# LMAT_AMT_V4.net
KiCad netlist of a schematic drawn in Altium Designer
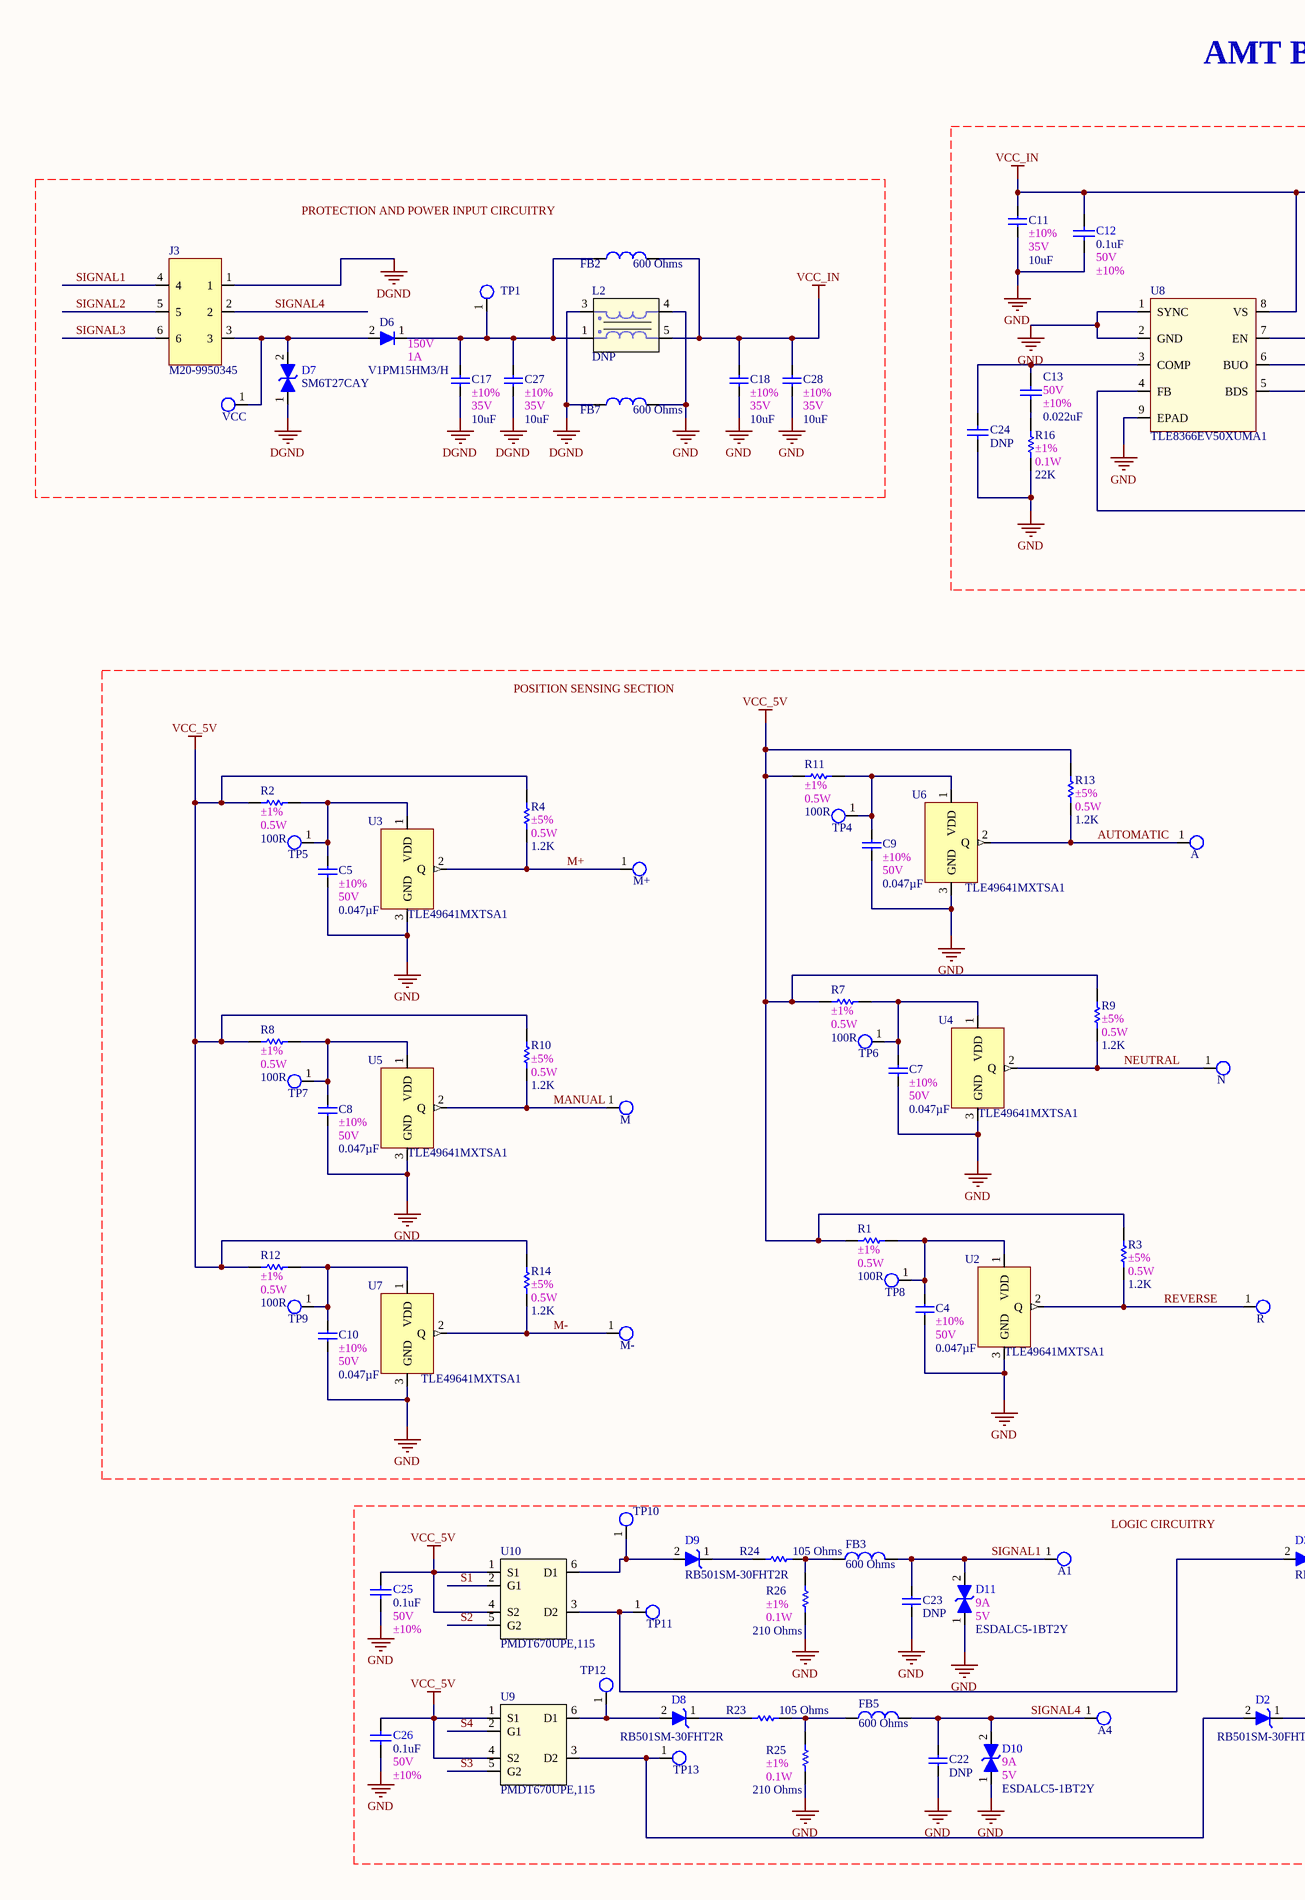
[diagram p0: LMAT_AMT_V4.SchDoc, left]
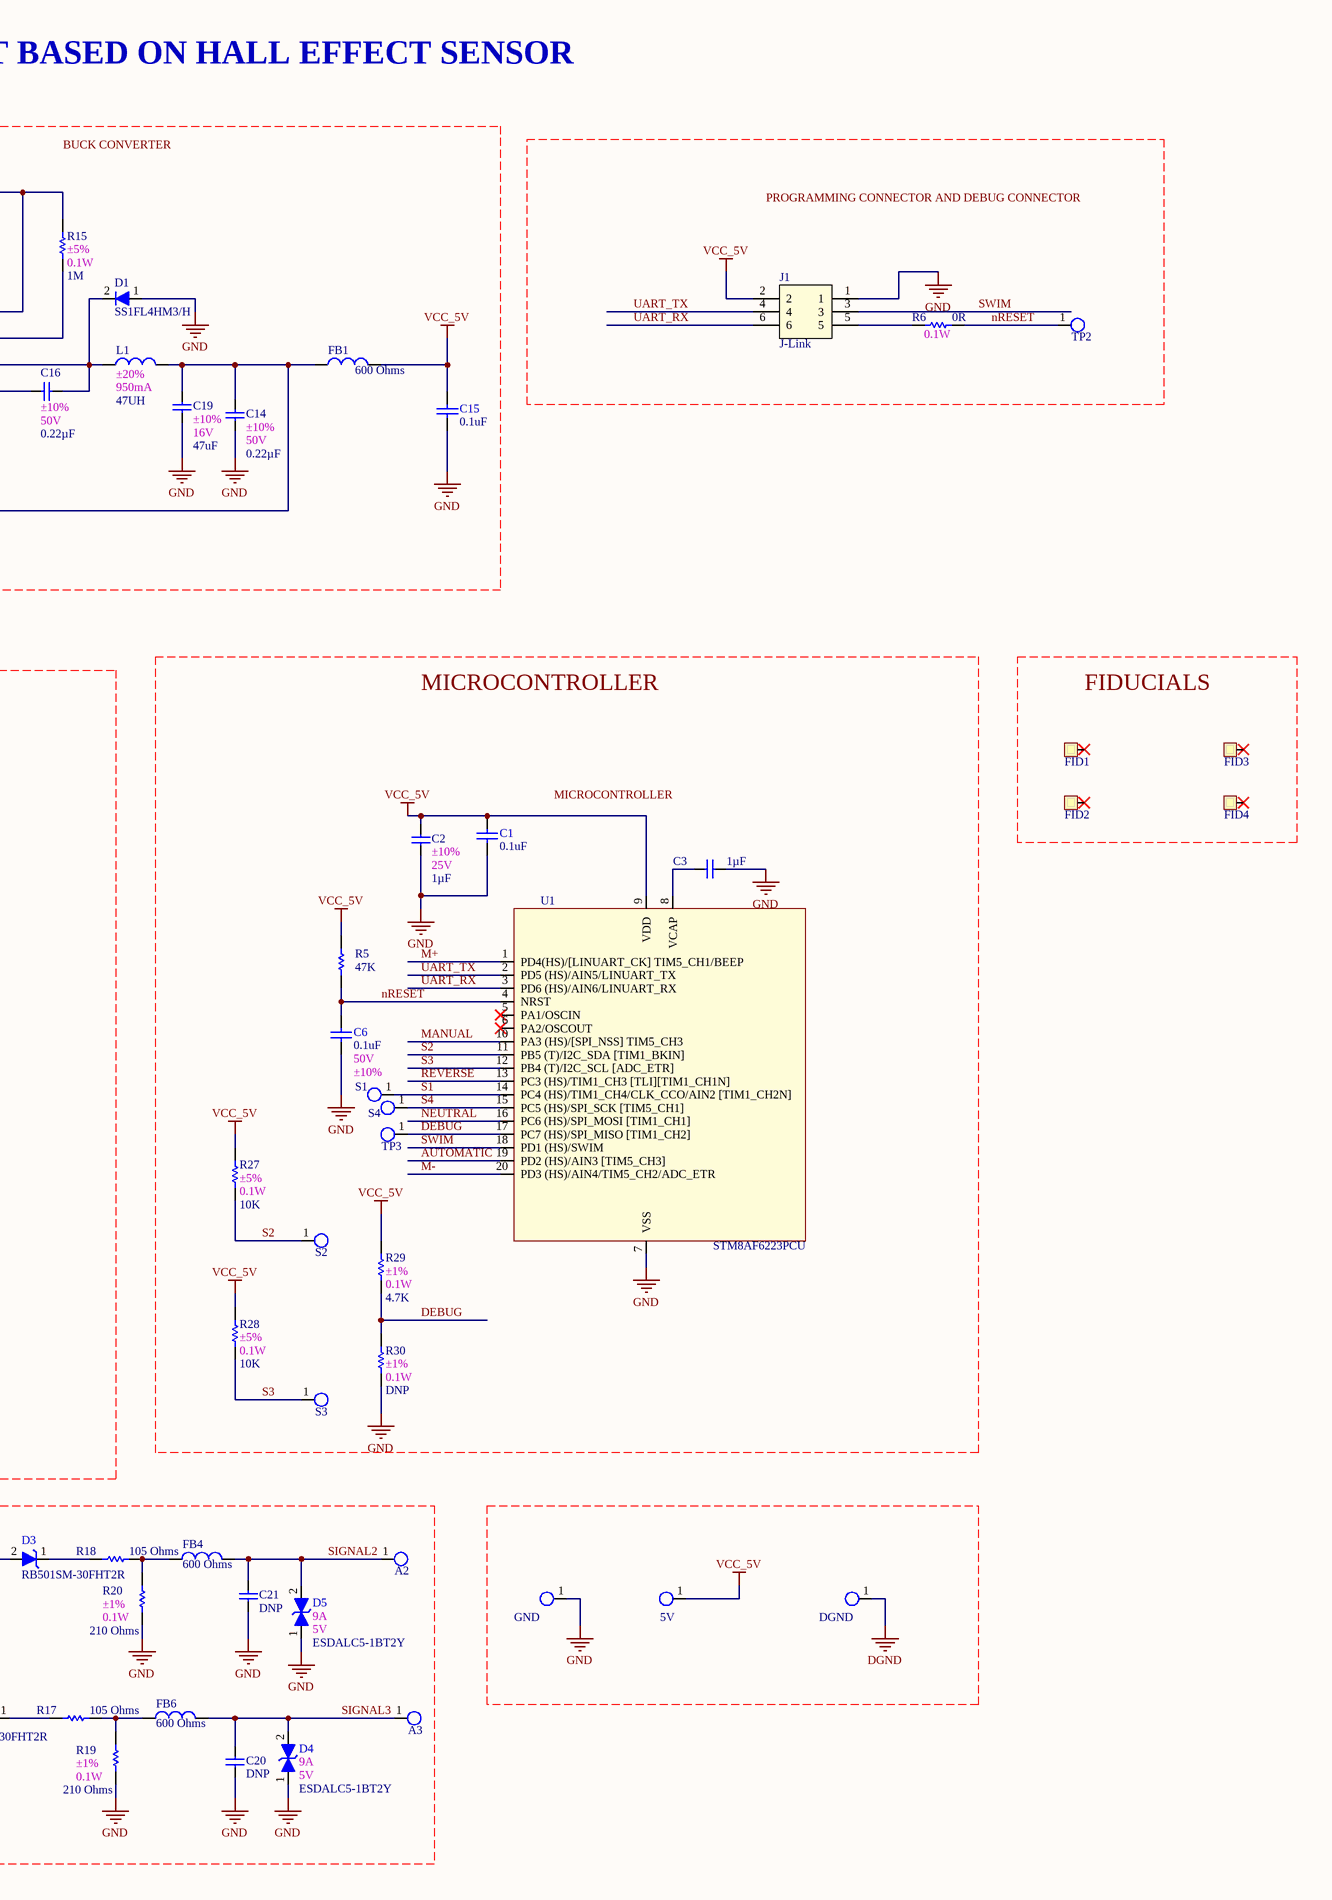
[diagram p1: LMAT_AMT_V4.SchDoc, right]

(export (version "E")
  (design (tool "Eeschema 10.0.6"))
  (components
    (comp (ref "5V")
      (value "Test Point- 35mil")
      (footprint "TP_40X40")
      (fields (field (name "INTERNAL PART NUMBER") "EMS-TP35MIL-S"))
      (libsource (lib "Integrated_Master_Library") (part "EMS-TP35MIL-S"))
    )
    (comp (ref "A")
      (value "Test Point- 35mil")
      (footprint "TP_40X40")
      (fields (field (name "INTERNAL PART NUMBER") "EMS-TP35MIL-S"))
      (libsource (lib "Integrated_Master_Library") (part "EMS-TP35MIL-S"))
    )
    (comp (ref "A1")
      (value "Test Point- 35mil")
      (footprint "TP_40X40")
      (fields (field (name "INTERNAL PART NUMBER") "EMS-TP35MIL-S"))
      (libsource (lib "Integrated_Master_Library") (part "EMS-TP35MIL-S"))
    )
    (comp (ref "A2")
      (value "Test Point- 35mil")
      (footprint "TP_40X40")
      (fields (field (name "INTERNAL PART NUMBER") "EMS-TP35MIL-S"))
      (libsource (lib "Integrated_Master_Library") (part "EMS-TP35MIL-S"))
    )
    (comp (ref "A3")
      (value "Test Point- 35mil")
      (footprint "TP_40X40")
      (fields (field (name "INTERNAL PART NUMBER") "EMS-TP35MIL-S"))
      (libsource (lib "Integrated_Master_Library") (part "EMS-TP35MIL-S"))
    )
    (comp (ref "A4")
      (value "Test Point- 35mil")
      (footprint "TP_40X40")
      (fields (field (name "INTERNAL PART NUMBER") "EMS-TP35MIL-S"))
      (libsource (lib "Integrated_Master_Library") (part "EMS-TP35MIL-S"))
    )
    (comp (ref "C1")
      (value "0.1uF")
      (footprint "Masterlib_auto:SMDC0603")
      (description "CAP CER 0.1UF 50V 10% X7R 0603")
      (fields
        (field (name "MANUFACTURER PART NUMBER") "CGA3E2X7R1H104K080AA")
        (field (name "MANUFACTURER") "TDK Corporation")
      )
      (libsource (lib "Integrated_Master_Library") (part "ECA0U10K50V0-SC"))
    )
    (comp (ref "C2")
      (value "1µF")
      (footprint "Masterlib_auto:SMDC0603")
      (description "CAP CER 1UF 25V X7R 0603")
      (fields
        (field (name "MANUFACTURER") "TDK Corporation")
        (field (name "VENDOR PART NUMBER") "445-173628-1-ND")
        (field (name "2ND AUXILIARY FIELD") "±10%")
        (field (name "1ST AUXILIARY FIELD") "25V")
      )
      (libsource (lib "Integrated_Master_Library (3)") (part "ECA1U00L25V0-SC"))
    )
    (comp (ref "C3")
      (value "1µF")
      (footprint "Masterlib_auto:SMDC0603")
      (description "CAP CER 1UF 25V X7R 0603")
      (fields
        (field (name "MANUFACTURER") "TDK Corporation")
        (field (name "VENDOR PART NUMBER") "445-173628-1-ND")
      )
      (libsource (lib "Integrated_Master_Library (3)") (part "ECA1U00L25V0-SC"))
    )
    (comp (ref "C4")
      (value "0.047µF")
      (footprint "Masterlib_auto:SMDC0603")
      (description "CAP CER 0.047UF 50V X7R 0603")
      (fields
        (field (name "MANUFACTURER") "TDK Corporation")
        (field (name "VENDOR PART NUMBER") "445-5664-1-ND")
        (field (name "2ND AUXILIARY FIELD") "±10%")
        (field (name "1ST AUXILIARY FIELD") "50V")
      )
      (libsource (lib "Integrated_Master_Library") (part "ECA47N0L50V-SC"))
    )
    (comp (ref "C5")
      (value "0.047µF")
      (footprint "Masterlib_auto:SMDC0603")
      (description "CAP CER 0.047UF 50V X7R 0603")
      (fields
        (field (name "MANUFACTURER") "TDK Corporation")
        (field (name "VENDOR PART NUMBER") "445-5664-1-ND")
        (field (name "2ND AUXILIARY FIELD") "±10%")
        (field (name "1ST AUXILIARY FIELD") "50V")
      )
      (libsource (lib "Integrated_Master_Library") (part "ECA47N0L50V-SC"))
    )
    (comp (ref "C6")
      (value "0.1uF")
      (footprint "Masterlib_auto:SMDC0603")
      (description "CAP CER 0.1UF 50V 10% X7R 0603")
      (fields
        (field (name "MANUFACTURER PART NUMBER") "CGA3E2X7R1H104K080AA")
        (field (name "MANUFACTURER") "TDK Corporation")
        (field (name "1ST AUXILIARY FIELD") "50V")
        (field (name "2ND AUXILIARY FIELD") "±10%")
      )
      (libsource (lib "Integrated_Master_Library") (part "ECA0U10K50V0-SC"))
    )
    (comp (ref "C7")
      (value "0.047µF")
      (footprint "Masterlib_auto:SMDC0603")
      (description "CAP CER 0.047UF 50V X7R 0603")
      (fields
        (field (name "MANUFACTURER") "TDK Corporation")
        (field (name "VENDOR PART NUMBER") "445-5664-1-ND")
        (field (name "2ND AUXILIARY FIELD") "±10%")
        (field (name "1ST AUXILIARY FIELD") "50V")
      )
      (libsource (lib "Integrated_Master_Library") (part "ECA47N0L50V-SC"))
    )
    (comp (ref "C8")
      (value "0.047µF")
      (footprint "Masterlib_auto:SMDC0603")
      (description "CAP CER 0.047UF 50V X7R 0603")
      (fields
        (field (name "MANUFACTURER") "TDK Corporation")
        (field (name "VENDOR PART NUMBER") "445-5664-1-ND")
        (field (name "2ND AUXILIARY FIELD") "±10%")
        (field (name "1ST AUXILIARY FIELD") "50V")
      )
      (libsource (lib "Integrated_Master_Library") (part "ECA47N0L50V-SC"))
    )
    (comp (ref "C9")
      (value "0.047µF")
      (footprint "Masterlib_auto:SMDC0603")
      (description "CAP CER 0.047UF 50V X7R 0603")
      (fields
        (field (name "MANUFACTURER") "TDK Corporation")
        (field (name "VENDOR PART NUMBER") "445-5664-1-ND")
        (field (name "2ND AUXILIARY FIELD") "±10%")
        (field (name "1ST AUXILIARY FIELD") "50V")
      )
      (libsource (lib "Integrated_Master_Library") (part "ECA47N0L50V-SC"))
    )
    (comp (ref "C10")
      (value "0.047µF")
      (footprint "Masterlib_auto:SMDC0603")
      (description "CAP CER 0.047UF 50V X7R 0603")
      (fields
        (field (name "MANUFACTURER") "TDK Corporation")
        (field (name "VENDOR PART NUMBER") "445-5664-1-ND")
        (field (name "2ND AUXILIARY FIELD") "±10%")
        (field (name "1ST AUXILIARY FIELD") "50V")
      )
      (libsource (lib "Integrated_Master_Library") (part "ECA47N0L50V-SC"))
    )
    (comp (ref "C11")
      (value "10uF")
      (footprint "Master_Library:SMDC1206")
      (description "CAP CER 10UF 35V X7R 1206")
      (fields
        (field (name "MANUFACTURER") "TDK Corporation")
        (field (name "VENDOR PART NUMBER") "445-174428-1-ND")
        (field (name "2ND AUXILIARY FIELD") "±10%")
        (field (name "1ST AUXILIARY FIELD") "35V")
      )
      (libsource (lib "Master_ Library") (part "ECA10U0L35V0-SG"))
    )
    (comp (ref "C12")
      (value "0.1uF")
      (footprint "Masterlib_auto:SMDC0603")
      (description "CAP CER 0.1UF 50V 10% X7R 0603")
      (fields
        (field (name "MANUFACTURER PART NUMBER") "CGA3E2X7R1H104K080AA")
        (field (name "MANUFACTURER") "TDK Corporation")
        (field (name "1ST AUXILIARY FIELD") "50V")
        (field (name "2ND AUXILIARY FIELD") "±10%")
      )
      (libsource (lib "Integrated_Master_Library") (part "ECA0U10K50V0-SC"))
    )
    (comp (ref "C13")
      (value "0.022uF")
      (footprint "Masterlib_auto:SMDC0603")
      (description "CAP CER 0.022UF 50V 10% X7R 0603")
      (fields
        (field (name "MANUFACTURER PART NUMBER") "CGA3E2X7R1H223K080AA")
        (field (name "MANUFACTURER") "TDK Corporation")
        (field (name "1ST AUXILIARY FIELD") "50V")
        (field (name "2ND AUXILIARY FIELD") "±10%")
      )
      (libsource (lib "Integrated_Master_Library") (part "ECA0U022K50V0-SC"))
    )
    (comp (ref "C14")
      (value "0.22µF")
      (footprint "Masterlib_auto:SMDC0603")
      (description "CAP CER 0.22UF 50V X7R 0603")
      (fields
        (field (name "MANUFACTURER") "Murata Electronics North America")
        (field (name "VENDOR PART NUMBER") "490-14410-1-ND")
        (field (name "2ND AUXILIARY FIELD") "±10%")
        (field (name "1ST AUXILIARY FIELD") "50V")
      )
      (libsource (lib "Integrated_Master_Library (3)") (part "ECA0U22L50V0-SC"))
    )
    (comp (ref "C15")
      (value "0.1uF")
      (footprint "Masterlib_auto:SMDC0603")
      (description "CAP CER 0.1UF 50V 10% X7R 0603")
      (fields
        (field (name "MANUFACTURER PART NUMBER") "CGA3E2X7R1H104K080AA")
        (field (name "MANUFACTURER") "TDK Corporation")
      )
      (libsource (lib "Integrated_Master_Library") (part "ECA0U10K50V0-SC"))
    )
    (comp (ref "C16")
      (value "0.22µF")
      (footprint "Masterlib_auto:SMDC0603")
      (description "CAP CER 0.22UF 50V X7R 0603")
      (fields
        (field (name "MANUFACTURER") "Murata Electronics North America")
        (field (name "VENDOR PART NUMBER") "490-14410-1-ND")
        (field (name "2ND AUXILIARY FIELD") "±10%")
        (field (name "1ST AUXILIARY FIELD") "50V")
      )
      (libsource (lib "Integrated_Master_Library") (part "ECA0U22L50V0-SC"))
    )
    (comp (ref "C17")
      (value "10uF")
      (footprint "Master_Library:SMDC1206")
      (description "CAP CER 10UF 35V X7R 1206")
      (fields
        (field (name "MANUFACTURER") "TDK Corporation")
        (field (name "VENDOR PART NUMBER") "445-174428-1-ND")
        (field (name "2ND AUXILIARY FIELD") "±10%")
        (field (name "1ST AUXILIARY FIELD") "35V")
      )
      (libsource (lib "Master_ Library") (part "ECA10U0L35V0-SG"))
    )
    (comp (ref "C18")
      (value "10uF")
      (footprint "Master_Library:SMDC1206")
      (description "CAP CER 10UF 35V X7R 1206")
      (fields
        (field (name "MANUFACTURER") "TDK Corporation")
        (field (name "VENDOR PART NUMBER") "445-174428-1-ND")
        (field (name "2ND AUXILIARY FIELD") "±10%")
        (field (name "1ST AUXILIARY FIELD") "35V")
      )
      (libsource (lib "Master_ Library") (part "ECA10U0L35V0-SG"))
    )
    (comp (ref "C19")
      (value "47uF")
      (footprint "Master_Library:SMDC1210")
      (description "CAP CER 47UF 16V X6S 1210")
      (fields
        (field (name "MANUFACTURER") "Murata Electronics North America")
        (field (name "VENDOR PART NUMBER") "490-12494-1-ND")
        (field (name "2ND AUXILIARY FIELD") "±10%")
        (field (name "1ST AUXILIARY FIELD") "16V")
      )
      (libsource (lib "Automobile-ML") (part "ECA47U0L16V0-SH"))
    )
    (comp (ref "C20")
      (value "DNP")
      (footprint "Masterlib_auto:SMDC0603")
      (description "CAP CER 10000PF 50V X8R 0603")
      (fields
        (field (name "MANUFACTURER") "TDK Corporation")
        (field (name "VENDOR PART NUMBER") "445-5892-1-ND")
      )
      (libsource (lib "Automobile-ML") (part "ECA0U01L50V0-SC"))
    )
    (comp (ref "C21")
      (value "DNP")
      (footprint "Masterlib_auto:SMDC0603")
      (description "CAP CER 10000PF 50V X8R 0603")
      (fields
        (field (name "MANUFACTURER") "TDK Corporation")
        (field (name "VENDOR PART NUMBER") "445-5892-1-ND")
      )
      (libsource (lib "Automobile-ML") (part "ECA0U01L50V0-SC"))
    )
    (comp (ref "C22")
      (value "DNP")
      (footprint "Masterlib_auto:SMDC0603")
      (description "CAP CER 10000PF 50V X8R 0603")
      (fields
        (field (name "MANUFACTURER") "TDK Corporation")
        (field (name "VENDOR PART NUMBER") "445-5892-1-ND")
      )
      (libsource (lib "Automobile-ML") (part "ECA0U01L50V0-SC"))
    )
    (comp (ref "C23")
      (value "DNP")
      (footprint "Masterlib_auto:SMDC0603")
      (description "CAP CER 10000PF 50V X8R 0603")
      (fields
        (field (name "MANUFACTURER") "TDK Corporation")
        (field (name "VENDOR PART NUMBER") "445-5892-1-ND")
      )
      (libsource (lib "Automobile-ML") (part "ECA0U01L50V0-SC"))
    )
    (comp (ref "C24")
      (value "DNP")
      (footprint "Masterlib_auto:SMDC0603")
      (description "CAP CER 0.022UF 50V 10% X7R 0603")
      (fields
        (field (name "MANUFACTURER PART NUMBER") "CGA3E2X7R1H223K080AA")
        (field (name "MANUFACTURER") "TDK Corporation")
      )
      (libsource (lib "Integrated_Master_Library") (part "ECA0U022K50V0-SC"))
    )
    (comp (ref "C25")
      (value "0.1uF")
      (footprint "Masterlib_auto:SMDC0603")
      (description "CAP CER 0.1UF 50V 10% X7R 0603")
      (fields
        (field (name "MANUFACTURER PART NUMBER") "CGA3E2X7R1H104K080AA")
        (field (name "MANUFACTURER") "TDK Corporation")
        (field (name "1ST AUXILIARY FIELD") "50V")
        (field (name "2ND AUXILIARY FIELD") "±10%")
      )
      (libsource (lib "Integrated_Master_Library") (part "ECA0U10K50V0-SC"))
    )
    (comp (ref "C26")
      (value "0.1uF")
      (footprint "Masterlib_auto:SMDC0603")
      (description "CAP CER 0.1UF 50V 10% X7R 0603")
      (fields
        (field (name "MANUFACTURER PART NUMBER") "CGA3E2X7R1H104K080AA")
        (field (name "MANUFACTURER") "TDK Corporation")
        (field (name "1ST AUXILIARY FIELD") "50V")
        (field (name "2ND AUXILIARY FIELD") "±10%")
      )
      (libsource (lib "Integrated_Master_Library") (part "ECA0U10K50V0-SC"))
    )
    (comp (ref "C27")
      (value "10uF")
      (footprint "Master_Library:SMDC1206")
      (description "CAP CER 10UF 35V X7R 1206")
      (fields
        (field (name "MANUFACTURER") "TDK Corporation")
        (field (name "VENDOR PART NUMBER") "445-174428-1-ND")
        (field (name "2ND AUXILIARY FIELD") "±10%")
        (field (name "1ST AUXILIARY FIELD") "35V")
      )
      (libsource (lib "Master_ Library") (part "ECA10U0L35V0-SG"))
    )
    (comp (ref "C28")
      (value "10uF")
      (footprint "Master_Library:SMDC1206")
      (description "CAP CER 10UF 35V X7R 1206")
      (fields
        (field (name "MANUFACTURER") "TDK Corporation")
        (field (name "VENDOR PART NUMBER") "445-174428-1-ND")
        (field (name "2ND AUXILIARY FIELD") "±10%")
        (field (name "1ST AUXILIARY FIELD") "35V")
      )
      (libsource (lib "Master_ Library") (part "ECA10U0L35V0-SG"))
    )
    (comp (ref "D1")
      (value "SS1FL4HM3/H")
      (footprint "Masterlib_auto:SODFL370X110-2N")
      (description "DIODE SCHOTTKY 40V 1A DO-219AB")
      (fields
        (field (name "MANUFACTURER") "Vishay Semiconductor Diodes Division")
        (field (name "INTERNAL PART NUMBER") "EDDVS1A0040V0-S")
      )
      (libsource (lib "Integrated_Master_Library (3)") (part "EDDVS1A0040V0-S"))
    )
    (comp (ref "D2")
      (value "RB501SM-30FHT2R")
      (footprint "Masterlib_auto:SOD1700X70N-V2")
      (description "Diode Schottky 30V 100mA Surface Mount EMD2")
      (fields
        (field (name "MANUFACTURER") "Rohm Semiconductor")
        (field (name "INTERNAL PART NUMBER") "EDDR0A1030V0-S")
      )
      (libsource (lib "Integrated_Master_Library (3)") (part "EDDR0A1030V0-S"))
    )
    (comp (ref "D3")
      (value "RB501SM-30FHT2R")
      (footprint "Masterlib_auto:SOD1700X70N-V2")
      (description "Diode Schottky 30V 100mA Surface Mount EMD2")
      (fields
        (field (name "MANUFACTURER") "Rohm Semiconductor")
        (field (name "INTERNAL PART NUMBER") "EDDR0A1030V0-S")
      )
      (libsource (lib "Integrated_Master_Library (3)") (part "EDDR0A1030V0-S"))
    )
    (comp (ref "D4")
      (value "ESDALC5-1BT2Y")
      (footprint "Master_Library:SOD1510X40")
      (description "TVS DIODE 5V 17.5V SOD882T")
      (fields
        (field (name "MANUFACTURER") "STMicroelectronics")
        (field (name "INTERNAL PART NUMBER") "EDDST9A005V00-S")
        (field (name "2ND AUXILIARY FIELD") "9A")
        (field (name "1ST AUXILIARY FIELD") "5V")
      )
      (libsource (lib "Master_ Library") (part "EDDST9A005V00-S"))
    )
    (comp (ref "D5")
      (value "ESDALC5-1BT2Y")
      (footprint "Master_Library:SOD1510X40")
      (description "TVS DIODE 5V 17.5V SOD882T")
      (fields
        (field (name "MANUFACTURER") "STMicroelectronics")
        (field (name "INTERNAL PART NUMBER") "EDDST9A005V00-S")
        (field (name "2ND AUXILIARY FIELD") "9A")
        (field (name "1ST AUXILIARY FIELD") "5V")
      )
      (libsource (lib "Master_ Library") (part "EDDST9A005V00-S"))
    )
    (comp (ref "D6")
      (value "V1PM15HM3/H")
      (footprint "MICROSMP (DO-219AD)")
      (description "DIODE SCHOTTKY 150V 1A MICROSMP")
      (fields
        (field (name "MANUFACTURER") "Vishay Semiconductor Diodes Division")
        (field (name "INTERNAL PART NUMBER") "EDDVS1A00150V-S")
        (field (name "1ST AUXILIARY FIELD") "150V")
        (field (name "2ND AUXILIARY FIELD") "1A")
      )
      (libsource (lib "Master_ Library") (part "EDDVS1A00150V-S"))
    )
    (comp (ref "D7")
      (value "SM6T27CAY")
      (footprint "Masterlib_auto:DIOM4336X26B")
      (description "TVS DIODE 23.1V 48.3V SMB")
      (fields
        (field (name "MANUFACTURER") "STMicroelectronics")
        (field (name "INTERNAL PART NUMBER") "EDDST83A025V7-S")
      )
      (libsource (lib "Integrated_Master_Library") (part "EDDST83A025V7-S"))
    )
    (comp (ref "D8")
      (value "RB501SM-30FHT2R")
      (footprint "Masterlib_auto:SOD1700X70N-V2")
      (description "Diode Schottky 30V 100mA Surface Mount EMD2")
      (fields
        (field (name "MANUFACTURER") "Rohm Semiconductor")
        (field (name "INTERNAL PART NUMBER") "EDDR0A1030V0-S")
      )
      (libsource (lib "Integrated_Master_Library (3)") (part "EDDR0A1030V0-S"))
    )
    (comp (ref "D9")
      (value "RB501SM-30FHT2R")
      (footprint "Masterlib_auto:SOD1700X70N-V2")
      (description "Diode Schottky 30V 100mA Surface Mount EMD2")
      (fields
        (field (name "MANUFACTURER") "Rohm Semiconductor")
        (field (name "INTERNAL PART NUMBER") "EDDR0A1030V0-S")
      )
      (libsource (lib "Integrated_Master_Library (3)") (part "EDDR0A1030V0-S"))
    )
    (comp (ref "D10")
      (value "ESDALC5-1BT2Y")
      (footprint "Master_Library:SOD1510X40")
      (description "TVS DIODE 5V 17.5V SOD882T")
      (fields
        (field (name "MANUFACTURER") "STMicroelectronics")
        (field (name "INTERNAL PART NUMBER") "EDDST9A005V00-S")
        (field (name "2ND AUXILIARY FIELD") "9A")
        (field (name "1ST AUXILIARY FIELD") "5V")
      )
      (libsource (lib "Master_ Library") (part "EDDST9A005V00-S"))
    )
    (comp (ref "D11")
      (value "ESDALC5-1BT2Y")
      (footprint "Master_Library:SOD1510X40")
      (description "TVS DIODE 5V 17.5V SOD882T")
      (fields
        (field (name "MANUFACTURER") "STMicroelectronics")
        (field (name "INTERNAL PART NUMBER") "EDDST9A005V00-S")
        (field (name "2ND AUXILIARY FIELD") "9A")
        (field (name "1ST AUXILIARY FIELD") "5V")
      )
      (libsource (lib "Master_ Library") (part "EDDST9A005V00-S"))
    )
    (comp (ref "DGND")
      (value "Test Point- 35mil")
      (footprint "TP_40X40")
      (fields (field (name "INTERNAL PART NUMBER") "EMS-TP35MIL-S"))
      (libsource (lib "Integrated_Master_Library") (part "EMS-TP35MIL-S"))
    )
    (comp (ref "FB1")
      (value "600 Ohms")
      (footprint "SMDL0603")
      (description "FERRITE BEAD 600 OHM 0603 1LN")
      (fields
        (field (name "MANUFACTURER") "Würth Elektronik")
        (field (name "INTERNAL PART NUMBER") "EIN600R1A00-SC")
      )
      (libsource (lib "Master_ Library") (part "EIN600R1A00-SC"))
    )
    (comp (ref "FB2")
      (value "600 Ohms")
      (footprint "SMDL0603")
      (description "FERRITE BEAD 600 OHM 0603 1LN")
      (fields
        (field (name "MANUFACTURER") "Würth Elektronik")
        (field (name "INTERNAL PART NUMBER") "EIN600R1A00-SC")
      )
      (libsource (lib "Master_ Library") (part "EIN600R1A00-SC"))
    )
    (comp (ref "FB3")
      (value "600 Ohms")
      (footprint "SMDL0603")
      (description "FERRITE BEAD 600 OHM 0603 1LN")
      (fields
        (field (name "MANUFACTURER") "Würth Elektronik")
        (field (name "INTERNAL PART NUMBER") "EIN600R1A00-SC")
      )
      (libsource (lib "Master_ Library") (part "EIN600R1A00-SC"))
    )
    (comp (ref "FB4")
      (value "600 Ohms")
      (footprint "SMDL0603")
      (description "FERRITE BEAD 600 OHM 0603 1LN")
      (fields
        (field (name "MANUFACTURER") "Würth Elektronik")
        (field (name "INTERNAL PART NUMBER") "EIN600R1A00-SC")
      )
      (libsource (lib "Master_ Library") (part "EIN600R1A00-SC"))
    )
    (comp (ref "FB5")
      (value "600 Ohms")
      (footprint "SMDL0603")
      (description "FERRITE BEAD 600 OHM 0603 1LN")
      (fields
        (field (name "MANUFACTURER") "Würth Elektronik")
        (field (name "INTERNAL PART NUMBER") "EIN600R1A00-SC")
      )
      (libsource (lib "Master_ Library") (part "EIN600R1A00-SC"))
    )
    (comp (ref "FB6")
      (value "600 Ohms")
      (footprint "SMDL0603")
      (description "FERRITE BEAD 600 OHM 0603 1LN")
      (fields
        (field (name "MANUFACTURER") "Würth Elektronik")
        (field (name "INTERNAL PART NUMBER") "EIN600R1A00-SC")
      )
      (libsource (lib "Master_ Library") (part "EIN600R1A00-SC"))
    )
    (comp (ref "FB7")
      (value "600 Ohms")
      (footprint "SMDL0603")
      (description "FERRITE BEAD 600 OHM 0603 1LN")
      (fields
        (field (name "MANUFACTURER") "Würth Elektronik")
        (field (name "INTERNAL PART NUMBER") "EIN600R1A00-SC")
      )
      (libsource (lib "Master_ Library") (part "EIN600R1A00-SC"))
    )
    (comp (ref "FID1")
      (value "FID40X40")
      (footprint "Master_Library:FID40X40")
      (libsource (lib "Master_ Library") (part "FID_40X40"))
    )
    (comp (ref "FID2")
      (value "FID40X40")
      (footprint "Master_Library:FID40X40")
      (libsource (lib "Master_ Library") (part "FID_40X40"))
    )
    (comp (ref "FID3")
      (value "FID40X40")
      (footprint "Master_Library:FID40X40")
      (libsource (lib "Master_ Library") (part "FID_40X40"))
    )
    (comp (ref "FID4")
      (value "FID40X40")
      (footprint "Master_Library:FID40X40")
      (libsource (lib "Master_ Library") (part "FID_40X40"))
    )
    (comp (ref "GND")
      (value "Test Point- 35mil")
      (footprint "TP_40X40")
      (fields (field (name "INTERNAL PART NUMBER") "EMS-TP35MIL-S"))
      (libsource (lib "Integrated_Master_Library") (part "EMS-TP35MIL-S"))
    )
    (comp (ref "J1")
      (value "J-LINK 6-PIN NEEDLE ADAPTER")
      (footprint "PRG_8.06.16 J-LINK 6-PIN NEEDLE ADAPTER")
      (fields
        (field (name "INTERNAL PART NUMBER") "EMS-8.06.16 J-LINK 6-PIN NEEDLE ADAPTER")
        (field (name "MANUFACTURER") "Segger Microcontroller Systems")
        (field (name "VENDOR PART NUMBER") "899-1051-ND")
        (field (name "1ST AUXILIARY FIELD") "J-Link")
      )
      (libsource (lib "Integrated_Master_Library") (part "EMS-8.06.16 J-LINK 6-PIN NEEDLE ADAPTER"))
    )
    (comp (ref "J3")
      (value "CONN HEADER R/A 6POS 2.54MM")
      (footprint "Masterlib_auto:HDRRA6W86P254_2X3_1344X254X528P_Modified")
      (fields
        (field (name "MANUFACTURER") "Harwin Inc.")
        (field (name "INTERNAL PART NUMBER") "ECN-M20-9950345-0003-0060")
        (field (name "VENDOR PART NUMBER") "952-2092-ND")
        (field (name "MANUFACTURER PART NUMBER") "M20-9950345")
      )
      (libsource (lib "Automobile-ML") (part "ECN-M20-9950345-0003-0060"))
    )
    (comp (ref "L1")
      (value "47UH")
      (footprint "Master_Library:INDC4949X310N")
      (description "FIXED IND 47UH 700MA 422.5 MOHM")
      (fields
        (field (name "MANUFACTURER") "Taiyo Yuden")
        (field (name "VENDOR PART NUMBER") "587-3604-1-ND")
        (field (name "2ND AUXILIARY FIELD") "±20%")
        (field (name "1ST AUXILIARY FIELD") "950mA")
      )
      (libsource (lib "Automobile-ML") (part "EIN47U0N950M-S"))
    )
    (comp (ref "L2")
      (value "DNP")
      (footprint "Master_Library:EMS_744212331")
      (description "CMC 330UH 300MA 2LN 2 KOHM SMD")
      (fields
        (field (name "MANUFACTURER") "Würth Elektronik")
        (field (name "INTERNAL PART NUMBER") "EIN330U300M-S")
      )
      (libsource (lib "Master_ Library") (part "EIN330U300M-S"))
    )
    (comp (ref "M")
      (value "Test Point- 35mil")
      (footprint "TP_40X40")
      (fields (field (name "INTERNAL PART NUMBER") "EMS-TP35MIL-S"))
      (libsource (lib "Integrated_Master_Library") (part "EMS-TP35MIL-S"))
    )
    (comp (ref "M+")
      (value "Test Point- 35mil")
      (footprint "TP_40X40")
      (fields (field (name "INTERNAL PART NUMBER") "EMS-TP35MIL-S"))
      (libsource (lib "Integrated_Master_Library") (part "EMS-TP35MIL-S"))
    )
    (comp (ref "M-")
      (value "Test Point- 35mil")
      (footprint "TP_40X40")
      (fields (field (name "INTERNAL PART NUMBER") "EMS-TP35MIL-S"))
      (libsource (lib "Integrated_Master_Library") (part "EMS-TP35MIL-S"))
    )
    (comp (ref "N")
      (value "Test Point- 35mil")
      (footprint "TP_40X40")
      (fields (field (name "INTERNAL PART NUMBER") "EMS-TP35MIL-S"))
      (libsource (lib "Integrated_Master_Library") (part "EMS-TP35MIL-S"))
    )
    (comp (ref "R")
      (value "Test Point- 35mil")
      (footprint "TP_40X40")
      (fields (field (name "INTERNAL PART NUMBER") "EMS-TP35MIL-S"))
      (libsource (lib "Integrated_Master_Library") (part "EMS-TP35MIL-S"))
    )
    (comp (ref "R1")
      (value "100R")
      (footprint "Masterlib_auto:SMDR0805")
      (description "RES SMD 100 OHM 1% 1/2W 0805")
      (fields
        (field (name "MANUFACTURER PART NUMBER") "ERJ-P06F1000V")
        (field (name "MANUFACTURER") "Panasonic Electronic Components")
        (field (name "2ND AUXILIARY FIELD") "±1%")
        (field (name "1ST AUXILIARY FIELD") "0.5W")
      )
      (libsource (lib "Automobile-ML") (part "ERE100RG120-SE"))
    )
    (comp (ref "R2")
      (value "100R")
      (footprint "Masterlib_auto:SMDR0805")
      (description "RES SMD 100 OHM 1% 1/2W 0805")
      (fields
        (field (name "MANUFACTURER PART NUMBER") "ERJ-P06F1000V")
        (field (name "MANUFACTURER") "Panasonic Electronic Components")
        (field (name "2ND AUXILIARY FIELD") "±1%")
        (field (name "1ST AUXILIARY FIELD") "0.5W")
      )
      (libsource (lib "Automobile-ML") (part "ERE100RG120-SE"))
    )
    (comp (ref "R3")
      (value "1.2K")
      (footprint "Masterlib_auto:SMDR0805")
      (description "RES SMD 1.2K OHM 5% 1/2W 0805")
      (fields
        (field (name "MANUFACTURER") "Panasonic Electronic Components")
        (field (name "VENDOR PART NUMBER") "P1.2KADCT-ND")
        (field (name "2ND AUXILIARY FIELD") "±5%")
        (field (name "1ST AUXILIARY FIELD") "0.5W")
      )
      (libsource (lib "Integrated_Master_Library") (part "ERE1K20G102-SE"))
    )
    (comp (ref "R4")
      (value "1.2K")
      (footprint "Masterlib_auto:SMDR0805")
      (description "RES SMD 1.2K OHM 5% 1/2W 0805")
      (fields
        (field (name "MANUFACTURER") "Panasonic Electronic Components")
        (field (name "VENDOR PART NUMBER") "P1.2KADCT-ND")
        (field (name "2ND AUXILIARY FIELD") "±5%")
        (field (name "1ST AUXILIARY FIELD") "0.5W")
      )
      (libsource (lib "Integrated_Master_Library") (part "ERE1K20G102-SE"))
    )
    (comp (ref "R5")
      (value "47K")
      (footprint "Masterlib_auto:SMDR0603")
      (description "RES SMD 47K OHM 1% 1/10W 0603")
      (fields (field (name "MANUFACTURER") "Yageo") (field (name "VENDOR PART NUMBER") "YAG2129CT-ND"))
      (libsource (lib "Integrated_Master_Library (3)") (part "ERE47K0G110-SC"))
    )
    (comp (ref "R6")
      (value "0R")
      (footprint "Masterlib_auto:SMDR0603")
      (description "RES SMD 0.0OHM JUMPER 1/10W 0603")
      (fields
        (field (name "MANUFACTURER PART NUMBER") "ERJ-3GEY0R00V")
        (field (name "MANUFACTURER") "Panasonic Electronic Components")
        (field (name "1ST AUXILIARY FIELD") "0.1W")
      )
      (libsource (lib "Integrated_Master_Library") (part "ERE0R00110-SC"))
    )
    (comp (ref "R7")
      (value "100R")
      (footprint "Masterlib_auto:SMDR0805")
      (description "RES SMD 100 OHM 1% 1/2W 0805")
      (fields
        (field (name "MANUFACTURER PART NUMBER") "ERJ-P06F1000V")
        (field (name "MANUFACTURER") "Panasonic Electronic Components")
        (field (name "2ND AUXILIARY FIELD") "±1%")
        (field (name "1ST AUXILIARY FIELD") "0.5W")
      )
      (libsource (lib "Automobile-ML") (part "ERE100RG120-SE"))
    )
    (comp (ref "R8")
      (value "100R")
      (footprint "Masterlib_auto:SMDR0805")
      (description "RES SMD 100 OHM 1% 1/2W 0805")
      (fields
        (field (name "MANUFACTURER PART NUMBER") "ERJ-P06F1000V")
        (field (name "MANUFACTURER") "Panasonic Electronic Components")
        (field (name "2ND AUXILIARY FIELD") "±1%")
        (field (name "1ST AUXILIARY FIELD") "0.5W")
      )
      (libsource (lib "Automobile-ML") (part "ERE100RG120-SE"))
    )
    (comp (ref "R9")
      (value "1.2K")
      (footprint "Masterlib_auto:SMDR0805")
      (description "RES SMD 1.2K OHM 5% 1/2W 0805")
      (fields
        (field (name "MANUFACTURER") "Panasonic Electronic Components")
        (field (name "VENDOR PART NUMBER") "P1.2KADCT-ND")
        (field (name "2ND AUXILIARY FIELD") "±5%")
        (field (name "1ST AUXILIARY FIELD") "0.5W")
      )
      (libsource (lib "Integrated_Master_Library") (part "ERE1K20G102-SE"))
    )
    (comp (ref "R10")
      (value "1.2K")
      (footprint "Masterlib_auto:SMDR0805")
      (description "RES SMD 1.2K OHM 5% 1/2W 0805")
      (fields
        (field (name "MANUFACTURER") "Panasonic Electronic Components")
        (field (name "VENDOR PART NUMBER") "P1.2KADCT-ND")
        (field (name "2ND AUXILIARY FIELD") "±5%")
        (field (name "1ST AUXILIARY FIELD") "0.5W")
      )
      (libsource (lib "Integrated_Master_Library") (part "ERE1K20G102-SE"))
    )
    (comp (ref "R11")
      (value "100R")
      (footprint "Masterlib_auto:SMDR0805")
      (description "RES SMD 100 OHM 1% 1/2W 0805")
      (fields
        (field (name "MANUFACTURER PART NUMBER") "ERJ-P06F1000V")
        (field (name "MANUFACTURER") "Panasonic Electronic Components")
        (field (name "2ND AUXILIARY FIELD") "±1%")
        (field (name "1ST AUXILIARY FIELD") "0.5W")
      )
      (libsource (lib "Automobile-ML") (part "ERE100RG120-SE"))
    )
    (comp (ref "R12")
      (value "100R")
      (footprint "Masterlib_auto:SMDR0805")
      (description "RES SMD 100 OHM 1% 1/2W 0805")
      (fields
        (field (name "MANUFACTURER PART NUMBER") "ERJ-P06F1000V")
        (field (name "MANUFACTURER") "Panasonic Electronic Components")
        (field (name "2ND AUXILIARY FIELD") "±1%")
        (field (name "1ST AUXILIARY FIELD") "0.5W")
      )
      (libsource (lib "Automobile-ML") (part "ERE100RG120-SE"))
    )
    (comp (ref "R13")
      (value "1.2K")
      (footprint "Masterlib_auto:SMDR0805")
      (description "RES SMD 1.2K OHM 5% 1/2W 0805")
      (fields
        (field (name "MANUFACTURER") "Panasonic Electronic Components")
        (field (name "VENDOR PART NUMBER") "P1.2KADCT-ND")
        (field (name "2ND AUXILIARY FIELD") "±5%")
        (field (name "1ST AUXILIARY FIELD") "0.5W")
      )
      (libsource (lib "Integrated_Master_Library") (part "ERE1K20G102-SE"))
    )
    (comp (ref "R14")
      (value "1.2K")
      (footprint "Masterlib_auto:SMDR0805")
      (description "RES SMD 1.2K OHM 5% 1/2W 0805")
      (fields
        (field (name "MANUFACTURER") "Panasonic Electronic Components")
        (field (name "VENDOR PART NUMBER") "P1.2KADCT-ND")
        (field (name "2ND AUXILIARY FIELD") "±5%")
        (field (name "1ST AUXILIARY FIELD") "0.5W")
      )
      (libsource (lib "Integrated_Master_Library") (part "ERE1K20G102-SE"))
    )
    (comp (ref "R15")
      (value "1M")
      (footprint "Masterlib_auto:SMDR0603")
      (description "RES SMD 1M OHM 5% 1/10W 0603")
      (fields
        (field (name "MANUFACTURER") "Vishay Dale")
        (field (name "VENDOR PART NUMBER") "541-2216-1-ND")
        (field (name "2ND AUXILIARY FIELD") "±5%")
        (field (name "1ST AUXILIARY FIELD") "0.1W")
      )
      (libsource (lib "Automobile-ML") (part "ERE1M00K110-SC"))
    )
    (comp (ref "R16")
      (value "22K")
      (footprint "Masterlib_auto:SMDR0603")
      (description "RES SMD 22K OHM 1% 1/10W 0603")
      (fields
        (field (name "MANUFACTURER") "Panasonic Electronic Components")
        (field (name "VENDOR PART NUMBER") "P22.0KHCT-ND")
        (field (name "2ND AUXILIARY FIELD") "±1%")
        (field (name "1ST AUXILIARY FIELD") "0.1W")
      )
      (libsource (lib "Automobile-ML") (part "ERE22K0G110-SC"))
    )
    (comp (ref "R17")
      (value "105 Ohms")
      (footprint "Masterlib_auto:SMDR0603")
      (description "RES SMD 105 OHM 1% 1/10W 0603")
      (fields
        (field (name "MANUFACTURER") "Panasonic Electronic Components")
        (field (name "VENDOR PART NUMBER") "P105HCT-ND")
      )
      (libsource (lib "Automobile-ML") (part "ERE105RG110-SC"))
    )
    (comp (ref "R18")
      (value "105 Ohms")
      (footprint "Masterlib_auto:SMDR0603")
      (description "RES SMD 105 OHM 1% 1/10W 0603")
      (fields
        (field (name "MANUFACTURER") "Panasonic Electronic Components")
        (field (name "VENDOR PART NUMBER") "P105HCT-ND")
      )
      (libsource (lib "Automobile-ML") (part "ERE105RG110-SC"))
    )
    (comp (ref "R19")
      (value "210 Ohms")
      (footprint "Masterlib_auto:SMDR0603")
      (description "RES SMD 210 OHM 1% 1/10W 0603")
      (fields
        (field (name "MANUFACTURER") "Panasonic Electronic Components")
        (field (name "VENDOR PART NUMBER") "P210HCT-ND")
        (field (name "2ND AUXILIARY FIELD") "±1%")
        (field (name "1ST AUXILIARY FIELD") "0.1W")
      )
      (libsource (lib "Automobile-ML") (part "ERE210RG110-SC"))
    )
    (comp (ref "R20")
      (value "210 Ohms")
      (footprint "Masterlib_auto:SMDR0603")
      (description "RES SMD 210 OHM 1% 1/10W 0603")
      (fields
        (field (name "MANUFACTURER") "Panasonic Electronic Components")
        (field (name "VENDOR PART NUMBER") "P210HCT-ND")
        (field (name "2ND AUXILIARY FIELD") "±1%")
        (field (name "1ST AUXILIARY FIELD") "0.1W")
      )
      (libsource (lib "Automobile-ML") (part "ERE210RG110-SC"))
    )
    (comp (ref "R23")
      (value "105 Ohms")
      (footprint "Masterlib_auto:SMDR0603")
      (description "RES SMD 105 OHM 1% 1/10W 0603")
      (fields
        (field (name "MANUFACTURER") "Panasonic Electronic Components")
        (field (name "VENDOR PART NUMBER") "P105HCT-ND")
      )
      (libsource (lib "Automobile-ML") (part "ERE105RG110-SC"))
    )
    (comp (ref "R24")
      (value "105 Ohms")
      (footprint "Masterlib_auto:SMDR0603")
      (description "RES SMD 105 OHM 1% 1/10W 0603")
      (fields
        (field (name "MANUFACTURER") "Panasonic Electronic Components")
        (field (name "VENDOR PART NUMBER") "P105HCT-ND")
      )
      (libsource (lib "Automobile-ML") (part "ERE105RG110-SC"))
    )
    (comp (ref "R25")
      (value "210 Ohms")
      (footprint "Masterlib_auto:SMDR0603")
      (description "RES SMD 210 OHM 1% 1/10W 0603")
      (fields
        (field (name "MANUFACTURER") "Panasonic Electronic Components")
        (field (name "VENDOR PART NUMBER") "P210HCT-ND")
        (field (name "2ND AUXILIARY FIELD") "±1%")
        (field (name "1ST AUXILIARY FIELD") "0.1W")
      )
      (libsource (lib "Automobile-ML") (part "ERE210RG110-SC"))
    )
    (comp (ref "R26")
      (value "210 Ohms")
      (footprint "Masterlib_auto:SMDR0603")
      (description "RES SMD 210 OHM 1% 1/10W 0603")
      (fields
        (field (name "MANUFACTURER") "Panasonic Electronic Components")
        (field (name "VENDOR PART NUMBER") "P210HCT-ND")
        (field (name "2ND AUXILIARY FIELD") "±1%")
        (field (name "1ST AUXILIARY FIELD") "0.1W")
      )
      (libsource (lib "Automobile-ML") (part "ERE210RG110-SC"))
    )
    (comp (ref "R27")
      (value "10K")
      (footprint "Masterlib_auto:SMDR0402")
      (description "RES SMD 10K OHM 5% 1/10W 0402")
      (fields
        (field (name "MANUFACTURER") "Panasonic Electronic Components")
        (field (name "VENDOR PART NUMBER") "P10KJCT-ND")
        (field (name "2ND AUXILIARY FIELD") "±5%")
        (field (name "1ST AUXILIARY FIELD") "0.1W")
      )
      (libsource (lib "Automobile-ML") (part "ERE10K0K110-SB"))
    )
    (comp (ref "R28")
      (value "10K")
      (footprint "Masterlib_auto:SMDR0402")
      (description "RES SMD 10K OHM 5% 1/10W 0402")
      (fields
        (field (name "MANUFACTURER") "Panasonic Electronic Components")
        (field (name "VENDOR PART NUMBER") "P10KJCT-ND")
        (field (name "2ND AUXILIARY FIELD") "±5%")
        (field (name "1ST AUXILIARY FIELD") "0.1W")
      )
      (libsource (lib "Automobile-ML") (part "ERE10K0K110-SB"))
    )
    (comp (ref "R29")
      (value "4.7K")
      (footprint "Masterlib_auto:SMDR0402")
      (description "RES SMD 4.7K OHM 1% 1/10W 0402")
      (fields
        (field (name "MANUFACTURER") "Panasonic Electronic Components")
        (field (name "VENDOR PART NUMBER") "P4.70KLCT-ND")
        (field (name "2ND AUXILIARY FIELD") "±1%")
        (field (name "1ST AUXILIARY FIELD") "0.1W")
      )
      (libsource (lib "Automobile-ML") (part "ERE4K70G110-SB"))
    )
    (comp (ref "R30")
      (value "DNP")
      (footprint "Masterlib_auto:SMDR0402")
      (description "RES SMD 4.7K OHM 1% 1/10W 0402")
      (fields
        (field (name "MANUFACTURER") "Panasonic Electronic Components")
        (field (name "VENDOR PART NUMBER") "P4.70KLCT-ND")
        (field (name "2ND AUXILIARY FIELD") "±1%")
        (field (name "1ST AUXILIARY FIELD") "0.1W")
      )
      (libsource (lib "Automobile-ML") (part "ERE4K70G110-SB"))
    )
    (comp (ref "S1")
      (value "Test Point- 35mil")
      (footprint "TP_40X40")
      (fields (field (name "INTERNAL PART NUMBER") "EMS-TP35MIL-S"))
      (libsource (lib "Integrated_Master_Library") (part "EMS-TP35MIL-S"))
    )
    (comp (ref "S2")
      (value "Test Point- 35mil")
      (footprint "TP_40X40")
      (fields (field (name "INTERNAL PART NUMBER") "EMS-TP35MIL-S"))
      (libsource (lib "Integrated_Master_Library") (part "EMS-TP35MIL-S"))
    )
    (comp (ref "S3")
      (value "Test Point- 35mil")
      (footprint "TP_40X40")
      (fields (field (name "INTERNAL PART NUMBER") "EMS-TP35MIL-S"))
      (libsource (lib "Integrated_Master_Library") (part "EMS-TP35MIL-S"))
    )
    (comp (ref "S4")
      (value "Test Point- 35mil")
      (footprint "TP_40X40")
      (fields (field (name "INTERNAL PART NUMBER") "EMS-TP35MIL-S"))
      (libsource (lib "Integrated_Master_Library") (part "EMS-TP35MIL-S"))
    )
    (comp (ref "TP1")
      (value "Test Point- 35mil")
      (footprint "TP_40X40")
      (fields (field (name "INTERNAL PART NUMBER") "EMS-TP35MIL-S"))
      (libsource (lib "Integrated_Master_Library") (part "EMS-TP35MIL-S"))
    )
    (comp (ref "TP2")
      (value "Test Point- 35mil")
      (footprint "TP_40X40")
      (fields (field (name "INTERNAL PART NUMBER") "EMS-TP35MIL-S"))
      (libsource (lib "Integrated_Master_Library") (part "EMS-TP35MIL-S"))
    )
    (comp (ref "TP3")
      (value "Test Point- 35mil")
      (footprint "TP_40X40")
      (fields (field (name "INTERNAL PART NUMBER") "EMS-TP35MIL-S"))
      (libsource (lib "Integrated_Master_Library") (part "EMS-TP35MIL-S"))
    )
    (comp (ref "TP4")
      (value "Test Point- 35mil")
      (footprint "TP_40X40")
      (fields (field (name "INTERNAL PART NUMBER") "EMS-TP35MIL-S"))
      (libsource (lib "Integrated_Master_Library") (part "EMS-TP35MIL-S"))
    )
    (comp (ref "TP5")
      (value "Test Point- 35mil")
      (footprint "TP_40X40")
      (fields (field (name "INTERNAL PART NUMBER") "EMS-TP35MIL-S"))
      (libsource (lib "Integrated_Master_Library") (part "EMS-TP35MIL-S"))
    )
    (comp (ref "TP6")
      (value "Test Point- 35mil")
      (footprint "TP_40X40")
      (fields (field (name "INTERNAL PART NUMBER") "EMS-TP35MIL-S"))
      (libsource (lib "Integrated_Master_Library") (part "EMS-TP35MIL-S"))
    )
    (comp (ref "TP7")
      (value "Test Point- 35mil")
      (footprint "TP_40X40")
      (fields (field (name "INTERNAL PART NUMBER") "EMS-TP35MIL-S"))
      (libsource (lib "Integrated_Master_Library") (part "EMS-TP35MIL-S"))
    )
    (comp (ref "TP8")
      (value "Test Point- 35mil")
      (footprint "TP_40X40")
      (fields (field (name "INTERNAL PART NUMBER") "EMS-TP35MIL-S"))
      (libsource (lib "Integrated_Master_Library") (part "EMS-TP35MIL-S"))
    )
    (comp (ref "TP9")
      (value "Test Point- 35mil")
      (footprint "TP_40X40")
      (fields (field (name "INTERNAL PART NUMBER") "EMS-TP35MIL-S"))
      (libsource (lib "Integrated_Master_Library") (part "EMS-TP35MIL-S"))
    )
    (comp (ref "TP10")
      (value "Test Point- 35mil")
      (footprint "TP_40X40")
      (fields (field (name "INTERNAL PART NUMBER") "EMS-TP35MIL-S"))
      (libsource (lib "Integrated_Master_Library") (part "EMS-TP35MIL-S"))
    )
    (comp (ref "TP11")
      (value "Test Point- 35mil")
      (footprint "TP_40X40")
      (fields (field (name "INTERNAL PART NUMBER") "EMS-TP35MIL-S"))
      (libsource (lib "Integrated_Master_Library") (part "EMS-TP35MIL-S"))
    )
    (comp (ref "TP12")
      (value "Test Point- 35mil")
      (footprint "TP_40X40")
      (fields (field (name "INTERNAL PART NUMBER") "EMS-TP35MIL-S"))
      (libsource (lib "Integrated_Master_Library") (part "EMS-TP35MIL-S"))
    )
    (comp (ref "TP13")
      (value "Test Point- 35mil")
      (footprint "TP_40X40")
      (fields (field (name "INTERNAL PART NUMBER") "EMS-TP35MIL-S"))
      (libsource (lib "Integrated_Master_Library") (part "EMS-TP35MIL-S"))
    )
    (comp (ref "U1")
      (value "STM8AF6223PCU")
      (footprint "Masterlib_auto:SOP65P640X120-20N")
      (description "IC MCU 8BIT 8KB FLASH 20TSSOP")
      (fields
        (field (name "MANUFACTURER") "STMicroelectronics")
        (field (name "INTERNAL PART NUMBER") "EICSTMTSSOP-20-1691")
      )
      (libsource (lib "Integrated_Master_Library (3)") (part "EICSTMTSSOP-20-1691"))
    )
    (comp (ref "U2")
      (value "TLE49641MXTSA1")
      (footprint "Master_Library:SOT95P248X115-3N")
      (description "MAGNETIC SWITCH UNIPOLAR SOT23-3")
      (fields
        (field (name "MANUFACTURER") "Infineon Technologies")
        (field (name "VENDOR PART NUMBER") "TLE49641MXTSA1CT-ND")
      )
      (libsource (lib "Integrated_Master_Library") (part "EICITSOT23-3-1528"))
    )
    (comp (ref "U3")
      (value "TLE49641MXTSA1")
      (footprint "Master_Library:SOT95P248X115-3N")
      (description "MAGNETIC SWITCH UNIPOLAR SOT23-3")
      (fields
        (field (name "MANUFACTURER") "Infineon Technologies")
        (field (name "VENDOR PART NUMBER") "TLE49641MXTSA1CT-ND")
      )
      (libsource (lib "Integrated_Master_Library") (part "EICITSOT23-3-1528"))
    )
    (comp (ref "U4")
      (value "TLE49641MXTSA1")
      (footprint "Master_Library:SOT95P248X115-3N")
      (description "MAGNETIC SWITCH UNIPOLAR SOT23-3")
      (fields
        (field (name "MANUFACTURER") "Infineon Technologies")
        (field (name "VENDOR PART NUMBER") "TLE49641MXTSA1CT-ND")
      )
      (libsource (lib "Integrated_Master_Library") (part "EICITSOT23-3-1528"))
    )
    (comp (ref "U5")
      (value "TLE49641MXTSA1")
      (footprint "Master_Library:SOT95P248X115-3N")
      (description "MAGNETIC SWITCH UNIPOLAR SOT23-3")
      (fields
        (field (name "MANUFACTURER") "Infineon Technologies")
        (field (name "VENDOR PART NUMBER") "TLE49641MXTSA1CT-ND")
      )
      (libsource (lib "Integrated_Master_Library") (part "EICITSOT23-3-1528"))
    )
    (comp (ref "U6")
      (value "TLE49641MXTSA1")
      (footprint "Master_Library:SOT95P248X115-3N")
      (description "MAGNETIC SWITCH UNIPOLAR SOT23-3")
      (fields
        (field (name "MANUFACTURER") "Infineon Technologies")
        (field (name "VENDOR PART NUMBER") "TLE49641MXTSA1CT-ND")
      )
      (libsource (lib "Integrated_Master_Library") (part "EICITSOT23-3-1528"))
    )
    (comp (ref "U7")
      (value "TLE49641MXTSA1")
      (footprint "Master_Library:SOT95P248X115-3N")
      (description "MAGNETIC SWITCH UNIPOLAR SOT23-3")
      (fields
        (field (name "MANUFACTURER") "Infineon Technologies")
        (field (name "VENDOR PART NUMBER") "TLE49641MXTSA1CT-ND")
      )
      (libsource (lib "Integrated_Master_Library") (part "EICITSOT23-3-1528"))
    )
    (comp (ref "U8")
      (value "TLE8366EV50XUMA1")
      (footprint "Masterlib_auto:SOIC127P600X170_HS-9N")
      (description "IC REG BUCK 5V 1.8A 8DSO")
      (fields
        (field (name "MANUFACTURER") "Infineon Technologies")
        (field (name "INTERNAL PART NUMBER") "EICITSOIC-08-0001")
      )
      (libsource (lib "Automobile-ML") (part "EICITSOIC-08-0001"))
    )
    (comp (ref "U9")
      (value "PMDT670UPE,115")
      (footprint "PcbLib_AMT:SOTFL50P160X60-6N-PMDT670UPE,115")
      (description "MOSFET 2P-CH 20V 0.55A SOT666")
      (fields
        (field (name "MANUFACTURER") "Nexperia USA Inc.")
        (field (name "INTERNAL PART NUMBER") "EICNUSOT666-06-0004")
      )
      (libsource (lib "Automobile-ML") (part "EICNUSOT666-06-0004"))
    )
    (comp (ref "U10")
      (value "PMDT670UPE,115")
      (footprint "PcbLib_AMT:SOTFL50P160X60-6N-PMDT670UPE,115")
      (description "MOSFET 2P-CH 20V 0.55A SOT666")
      (fields
        (field (name "MANUFACTURER") "Nexperia USA Inc.")
        (field (name "INTERNAL PART NUMBER") "EICNUSOT666-06-0004")
      )
      (libsource (lib "Automobile-ML") (part "EICNUSOT666-06-0004"))
    )
    (comp (ref "VCC")
      (value "Test Point- 35mil")
      (footprint "TP_40X40")
      (fields (field (name "INTERNAL PART NUMBER") "EMS-TP35MIL-S"))
      (libsource (lib "Integrated_Master_Library") (part "EMS-TP35MIL-S"))
    )
  )
  (nets
    (net (code "1") (name "/AUTOMATIC") (class "Default")
      (node (ref "A") (pin "1") (pinfunction "1_1") (pintype "passive"))
      (node (ref "R13") (pin "2") (pinfunction "2_2") (pintype "passive"))
      (node (ref "U1") (pin "19") (pinfunction "PD2_(HS)/AIN3_[TIM5_CH3]_19") (pintype "passive"))
      (node (ref "U6") (pin "2") (pinfunction "Q_2") (pintype "output"))
    )
    (net (code "2") (name "/DEBUG") (class "Default")
      (node (ref "R29") (pin "1") (pinfunction "1_1") (pintype "passive"))
      (node (ref "R30") (pin "2") (pinfunction "2_2") (pintype "passive"))
      (node (ref "TP3") (pin "1") (pinfunction "1_1") (pintype "passive"))
      (node (ref "U1") (pin "17") (pinfunction "PC7_(HS)/SPI_MISO_[TIM1_CH2]_17") (pintype "passive"))
    )
    (net (code "3") (name "/M+") (class "Default")
      (node (ref "M+") (pin "1") (pinfunction "1_1") (pintype "passive"))
      (node (ref "R4") (pin "2") (pinfunction "2_2") (pintype "passive"))
      (node (ref "U1") (pin "1") (pinfunction "PD4(HS)/[LINUART_CK]_TIM5_CH1/BEEP_1") (pintype "passive"))
      (node (ref "U3") (pin "2") (pinfunction "Q_2") (pintype "output"))
    )
    (net (code "4") (name "/M-") (class "Default")
      (node (ref "M-") (pin "1") (pinfunction "1_1") (pintype "passive"))
      (node (ref "R14") (pin "2") (pinfunction "2_2") (pintype "passive"))
      (node (ref "U1") (pin "20") (pinfunction "PD3_(HS)/AIN4/TIM5_CH2/ADC_ETR_20") (pintype "passive"))
      (node (ref "U7") (pin "2") (pinfunction "Q_2") (pintype "output"))
    )
    (net (code "5") (name "/MANUAL") (class "Default")
      (node (ref "M") (pin "1") (pinfunction "1_1") (pintype "passive"))
      (node (ref "R10") (pin "2") (pinfunction "2_2") (pintype "passive"))
      (node (ref "U1") (pin "10") (pinfunction "PA3_(HS)/[SPI_NSS]_TIM5_CH3_10") (pintype "passive"))
      (node (ref "U5") (pin "2") (pinfunction "Q_2") (pintype "output"))
    )
    (net (code "6") (name "/NEUTRAL") (class "Default")
      (node (ref "N") (pin "1") (pinfunction "1_1") (pintype "passive"))
      (node (ref "R9") (pin "2") (pinfunction "2_2") (pintype "passive"))
      (node (ref "U1") (pin "16") (pinfunction "PC6_(HS)/SPI_MOSI_[TIM1_CH1]_16") (pintype "passive"))
      (node (ref "U4") (pin "2") (pinfunction "Q_2") (pintype "output"))
    )
    (net (code "7") (name "/REVERSE") (class "Default")
      (node (ref "R") (pin "1") (pinfunction "1_1") (pintype "passive"))
      (node (ref "R3") (pin "2") (pinfunction "2_2") (pintype "passive"))
      (node (ref "U1") (pin "13") (pinfunction "PC3_(HS)/TIM1_CH3_[TLI][TIM1_CH1N]_13") (pintype "passive"))
      (node (ref "U2") (pin "2") (pinfunction "Q_2") (pintype "output"))
    )
    (net (code "8") (name "/S1") (class "Default")
      (node (ref "S1") (pin "1") (pinfunction "1_1") (pintype "passive"))
      (node (ref "U1") (pin "14") (pinfunction "PC4_(HS)/TIM1_CH4/CLK_CCO/AIN2_[TIM1_CH2N]_14") (pintype "passive"))
      (node (ref "U10") (pin "2") (pinfunction "G1_2") (pintype "passive"))
    )
    (net (code "9") (name "/S2") (class "Default")
      (node (ref "R27") (pin "1") (pinfunction "1_1") (pintype "passive"))
      (node (ref "S2") (pin "1") (pinfunction "1_1") (pintype "passive"))
      (node (ref "U1") (pin "11") (pinfunction "PB5_(T)/I2C_SDA_[TIM1_BKIN]_11") (pintype "passive"))
      (node (ref "U10") (pin "5") (pinfunction "G2_5") (pintype "passive"))
    )
    (net (code "10") (name "/S3") (class "Default")
      (node (ref "R28") (pin "1") (pinfunction "1_1") (pintype "passive"))
      (node (ref "S3") (pin "1") (pinfunction "1_1") (pintype "passive"))
      (node (ref "U1") (pin "12") (pinfunction "PB4_(T)/I2C_SCL_[ADC_ETR]_12") (pintype "passive"))
      (node (ref "U9") (pin "5") (pinfunction "G2_5") (pintype "passive"))
    )
    (net (code "11") (name "/S4") (class "Default")
      (node (ref "S4") (pin "1") (pinfunction "1_1") (pintype "passive"))
      (node (ref "U1") (pin "15") (pinfunction "PC5_(HS)/SPI_SCK_[TIM5_CH1]_15") (pintype "passive"))
      (node (ref "U9") (pin "2") (pinfunction "G1_2") (pintype "passive"))
    )
    (net (code "12") (name "/SIGNAL1") (class "Default")
      (node (ref "A1") (pin "1") (pinfunction "1_1") (pintype "passive"))
      (node (ref "C23") (pin "2") (pinfunction "2_2") (pintype "passive"))
      (node (ref "D11") (pin "2") (pinfunction "2_2") (pintype "passive"))
      (node (ref "FB3") (pin "2") (pinfunction "2_2") (pintype "passive"))
      (node (ref "J3") (pin "4") (pinfunction "4_4") (pintype "passive"))
    )
    (net (code "13") (name "/SIGNAL2") (class "Default")
      (node (ref "A2") (pin "1") (pinfunction "1_1") (pintype "passive"))
      (node (ref "C21") (pin "2") (pinfunction "2_2") (pintype "passive"))
      (node (ref "D5") (pin "2") (pinfunction "2_2") (pintype "passive"))
      (node (ref "FB4") (pin "2") (pinfunction "2_2") (pintype "passive"))
      (node (ref "J3") (pin "5") (pinfunction "5_5") (pintype "passive"))
    )
    (net (code "14") (name "/SIGNAL3") (class "Default")
      (node (ref "A3") (pin "1") (pinfunction "1_1") (pintype "passive"))
      (node (ref "C20") (pin "2") (pinfunction "2_2") (pintype "passive"))
      (node (ref "D4") (pin "2") (pinfunction "2_2") (pintype "passive"))
      (node (ref "FB6") (pin "2") (pinfunction "2_2") (pintype "passive"))
      (node (ref "J3") (pin "6") (pinfunction "6_6") (pintype "passive"))
    )
    (net (code "15") (name "/SIGNAL4") (class "Default")
      (node (ref "A4") (pin "1") (pinfunction "1_1") (pintype "passive"))
      (node (ref "C22") (pin "2") (pinfunction "2_2") (pintype "passive"))
      (node (ref "D10") (pin "2") (pinfunction "2_2") (pintype "passive"))
      (node (ref "FB5") (pin "2") (pinfunction "2_2") (pintype "passive"))
      (node (ref "J3") (pin "2") (pinfunction "2_2") (pintype "passive"))
    )
    (net (code "16") (name "/SWIM") (class "Default")
      (node (ref "J1") (pin "3") (pinfunction "3_3") (pintype "passive"))
      (node (ref "U1") (pin "18") (pinfunction "PD1_(HS)/SWIM_18") (pintype "passive"))
    )
    (net (code "17") (name "/UART_RX") (class "Default")
      (node (ref "J1") (pin "6") (pinfunction "6_6") (pintype "passive"))
      (node (ref "U1") (pin "3") (pinfunction "PD6_(HS)/AIN6/LINUART_RX_3") (pintype "passive"))
    )
    (net (code "18") (name "/UART_TX") (class "Default")
      (node (ref "J1") (pin "4") (pinfunction "4_4") (pintype "passive"))
      (node (ref "U1") (pin "2") (pinfunction "PD5_(HS)/AIN5/LINUART_TX_2") (pintype "passive"))
    )
    (net (code "19") (name "/nRESET") (class "Default")
      (node (ref "C6") (pin "1") (pinfunction "1_1") (pintype "passive"))
      (node (ref "R5") (pin "1") (pinfunction "1_1") (pintype "passive"))
      (node (ref "R6") (pin "2") (pinfunction "2_2") (pintype "passive"))
      (node (ref "TP2") (pin "1") (pinfunction "1_1") (pintype "passive"))
      (node (ref "U1") (pin "4") (pinfunction "NRST_4") (pintype "passive"))
    )
    (net (code "20") (name "DGND") (class "Default")
      (node (ref "C17") (pin "1") (pinfunction "1_1") (pintype "passive"))
      (node (ref "C27") (pin "1") (pinfunction "1_1") (pintype "passive"))
      (node (ref "D7") (pin "1") (pinfunction "ANODE_1") (pintype "passive"))
      (node (ref "DGND") (pin "1") (pinfunction "1_1") (pintype "passive"))
      (node (ref "FB7") (pin "1") (pinfunction "1_1") (pintype "passive"))
      (node (ref "J3") (pin "1") (pinfunction "1_1") (pintype "passive"))
      (node (ref "L2") (pin "3") (pinfunction "3_3") (pintype "passive"))
    )
    (net (code "21") (name "GND") (class "Default")
      (node (ref "C1") (pin "2") (pinfunction "2_2") (pintype "passive"))
      (node (ref "C10") (pin "1") (pinfunction "1_1") (pintype "passive"))
      (node (ref "C11") (pin "1") (pinfunction "1_1") (pintype "passive"))
      (node (ref "C12") (pin "2") (pinfunction "2_2") (pintype "passive"))
      (node (ref "C14") (pin "1") (pinfunction "1_1") (pintype "passive"))
      (node (ref "C15") (pin "2") (pinfunction "2_2") (pintype "passive"))
      (node (ref "C18") (pin "1") (pinfunction "1_1") (pintype "passive"))
      (node (ref "C19") (pin "1") (pinfunction "1_1") (pintype "passive"))
      (node (ref "C2") (pin "1") (pinfunction "1_1") (pintype "passive"))
      (node (ref "C20") (pin "1") (pinfunction "1_1") (pintype "passive"))
      (node (ref "C21") (pin "1") (pinfunction "1_1") (pintype "passive"))
      (node (ref "C22") (pin "1") (pinfunction "1_1") (pintype "passive"))
      (node (ref "C23") (pin "1") (pinfunction "1_1") (pintype "passive"))
      (node (ref "C24") (pin "2") (pinfunction "2_2") (pintype "passive"))
      (node (ref "C25") (pin "2") (pinfunction "2_2") (pintype "passive"))
      (node (ref "C26") (pin "2") (pinfunction "2_2") (pintype "passive"))
      (node (ref "C28") (pin "1") (pinfunction "1_1") (pintype "passive"))
      (node (ref "C3") (pin "2") (pinfunction "2_2") (pintype "passive"))
      (node (ref "C4") (pin "1") (pinfunction "1_1") (pintype "passive"))
      (node (ref "C5") (pin "1") (pinfunction "1_1") (pintype "passive"))
      (node (ref "C6") (pin "2") (pinfunction "2_2") (pintype "passive"))
      (node (ref "C7") (pin "1") (pinfunction "1_1") (pintype "passive"))
      (node (ref "C8") (pin "1") (pinfunction "1_1") (pintype "passive"))
      (node (ref "C9") (pin "1") (pinfunction "1_1") (pintype "passive"))
      (node (ref "D1") (pin "1") (pinfunction "Cathode_1") (pintype "passive"))
      (node (ref "D10") (pin "1") (pinfunction "1_1") (pintype "passive"))
      (node (ref "D11") (pin "1") (pinfunction "1_1") (pintype "passive"))
      (node (ref "D4") (pin "1") (pinfunction "1_1") (pintype "passive"))
      (node (ref "D5") (pin "1") (pinfunction "1_1") (pintype "passive"))
      (node (ref "FB7") (pin "2") (pinfunction "2_2") (pintype "passive"))
      (node (ref "GND") (pin "1") (pinfunction "1_1") (pintype "passive"))
      (node (ref "J1") (pin "1") (pinfunction "1_1") (pintype "passive"))
      (node (ref "L2") (pin "4") (pinfunction "4_4") (pintype "passive"))
      (node (ref "R16") (pin "1") (pinfunction "1_1") (pintype "passive"))
      (node (ref "R19") (pin "2") (pinfunction "2_2") (pintype "passive"))
      (node (ref "R20") (pin "2") (pinfunction "2_2") (pintype "passive"))
      (node (ref "R25") (pin "2") (pinfunction "2_2") (pintype "passive"))
      (node (ref "R26") (pin "2") (pinfunction "2_2") (pintype "passive"))
      (node (ref "R30") (pin "1") (pinfunction "1_1") (pintype "passive"))
      (node (ref "U1") (pin "7") (pinfunction "VSS_7") (pintype "passive"))
      (node (ref "U2") (pin "3") (pinfunction "GND_3") (pintype "power_in"))
      (node (ref "U3") (pin "3") (pinfunction "GND_3") (pintype "power_in"))
      (node (ref "U4") (pin "3") (pinfunction "GND_3") (pintype "power_in"))
      (node (ref "U5") (pin "3") (pinfunction "GND_3") (pintype "power_in"))
      (node (ref "U6") (pin "3") (pinfunction "GND_3") (pintype "power_in"))
      (node (ref "U7") (pin "3") (pinfunction "GND_3") (pintype "power_in"))
      (node (ref "U8") (pin "1") (pinfunction "SYNC_1") (pintype "passive"))
      (node (ref "U8") (pin "2") (pinfunction "GND_2") (pintype "passive"))
      (node (ref "U8") (pin "9") (pinfunction "EPAD_9") (pintype "passive"))
    )
    (net (code "22") (name "Net-(C13-Pad2)") (class "Default")
      (node (ref "C13") (pin "2") (pinfunction "2_2") (pintype "passive"))
      (node (ref "R16") (pin "2") (pinfunction "2_2") (pintype "passive"))
    )
    (net (code "23") (name "Net-(D1-Anode)") (class "Default")
      (node (ref "C16") (pin "2") (pinfunction "2_2") (pintype "passive"))
      (node (ref "D1") (pin "2") (pinfunction "Anode_2") (pintype "passive"))
      (node (ref "L1") (pin "1") (pinfunction "1_1") (pintype "passive"))
      (node (ref "U8") (pin "6") (pinfunction "BUO_6") (pintype "passive"))
    )
    (net (code "24") (name "Net-(D2-ANODE)") (class "Default")
      (node (ref "D2") (pin "2") (pinfunction "ANODE_2") (pintype "passive"))
      (node (ref "TP13") (pin "1") (pinfunction "1_1") (pintype "passive"))
      (node (ref "U9") (pin "3") (pinfunction "D2_3") (pintype "passive"))
    )
    (net (code "25") (name "Net-(D2-CATHODE)") (class "Default")
      (node (ref "D2") (pin "1") (pinfunction "CATHODE_1") (pintype "passive"))
      (node (ref "R17") (pin "1") (pinfunction "1_1") (pintype "passive"))
    )
    (net (code "26") (name "Net-(D3-ANODE)") (class "Default")
      (node (ref "D3") (pin "2") (pinfunction "ANODE_2") (pintype "passive"))
      (node (ref "TP11") (pin "1") (pinfunction "1_1") (pintype "passive"))
      (node (ref "U10") (pin "3") (pinfunction "D2_3") (pintype "passive"))
    )
    (net (code "27") (name "Net-(D3-CATHODE)") (class "Default")
      (node (ref "D3") (pin "1") (pinfunction "CATHODE_1") (pintype "passive"))
      (node (ref "R18") (pin "1") (pinfunction "1_1") (pintype "passive"))
    )
    (net (code "28") (name "Net-(D6-Anode)") (class "Default")
      (node (ref "D6") (pin "2") (pinfunction "Anode_2") (pintype "passive"))
      (node (ref "D7") (pin "2") (pinfunction "CATHODE_2") (pintype "passive"))
      (node (ref "J3") (pin "3") (pinfunction "3_3") (pintype "passive"))
      (node (ref "VCC") (pin "1") (pinfunction "1_1") (pintype "passive"))
    )
    (net (code "29") (name "Net-(D6-Cathode)") (class "Default")
      (node (ref "C17") (pin "2") (pinfunction "2_2") (pintype "passive"))
      (node (ref "C27") (pin "2") (pinfunction "2_2") (pintype "passive"))
      (node (ref "D6") (pin "1") (pinfunction "Cathode_1") (pintype "passive"))
      (node (ref "FB2") (pin "1") (pinfunction "1_1") (pintype "passive"))
      (node (ref "L2") (pin "1") (pinfunction "1_1") (pintype "passive"))
      (node (ref "TP1") (pin "1") (pinfunction "1_1") (pintype "passive"))
    )
    (net (code "30") (name "Net-(D8-ANODE)") (class "Default")
      (node (ref "D8") (pin "2") (pinfunction "ANODE_2") (pintype "passive"))
      (node (ref "TP12") (pin "1") (pinfunction "1_1") (pintype "passive"))
      (node (ref "U9") (pin "6") (pinfunction "D1_6") (pintype "passive"))
    )
    (net (code "31") (name "Net-(D8-CATHODE)") (class "Default")
      (node (ref "D8") (pin "1") (pinfunction "CATHODE_1") (pintype "passive"))
      (node (ref "R23") (pin "1") (pinfunction "1_1") (pintype "passive"))
    )
    (net (code "32") (name "Net-(D9-ANODE)") (class "Default")
      (node (ref "D9") (pin "2") (pinfunction "ANODE_2") (pintype "passive"))
      (node (ref "TP10") (pin "1") (pinfunction "1_1") (pintype "passive"))
      (node (ref "U10") (pin "6") (pinfunction "D1_6") (pintype "passive"))
    )
    (net (code "33") (name "Net-(D9-CATHODE)") (class "Default")
      (node (ref "D9") (pin "1") (pinfunction "CATHODE_1") (pintype "passive"))
      (node (ref "R24") (pin "1") (pinfunction "1_1") (pintype "passive"))
    )
    (net (code "34") (name "Net-(FB3-Pad1)") (class "Default")
      (node (ref "FB3") (pin "1") (pinfunction "1_1") (pintype "passive"))
      (node (ref "R24") (pin "2") (pinfunction "2_2") (pintype "passive"))
      (node (ref "R26") (pin "1") (pinfunction "1_1") (pintype "passive"))
    )
    (net (code "35") (name "Net-(FB4-Pad1)") (class "Default")
      (node (ref "FB4") (pin "1") (pinfunction "1_1") (pintype "passive"))
      (node (ref "R18") (pin "2") (pinfunction "2_2") (pintype "passive"))
      (node (ref "R20") (pin "1") (pinfunction "1_1") (pintype "passive"))
    )
    (net (code "36") (name "Net-(FB5-Pad1)") (class "Default")
      (node (ref "FB5") (pin "1") (pinfunction "1_1") (pintype "passive"))
      (node (ref "R23") (pin "2") (pinfunction "2_2") (pintype "passive"))
      (node (ref "R25") (pin "1") (pinfunction "1_1") (pintype "passive"))
    )
    (net (code "37") (name "Net-(FB6-Pad1)") (class "Default")
      (node (ref "FB6") (pin "1") (pinfunction "1_1") (pintype "passive"))
      (node (ref "R17") (pin "2") (pinfunction "2_2") (pintype "passive"))
      (node (ref "R19") (pin "1") (pinfunction "1_1") (pintype "passive"))
    )
    (net (code "38") (name "Net-(J1-Pad5)") (class "Default")
      (node (ref "J1") (pin "5") (pinfunction "5_5") (pintype "passive"))
      (node (ref "R6") (pin "1") (pinfunction "1_1") (pintype "passive"))
    )
    (net (code "39") (name "Net-(U1-VCAP)") (class "Default")
      (node (ref "C3") (pin "1") (pinfunction "1_1") (pintype "passive"))
      (node (ref "U1") (pin "8") (pinfunction "VCAP_8") (pintype "passive"))
    )
    (net (code "40") (name "Net-(U2-VDD)") (class "Default")
      (node (ref "C4") (pin "2") (pinfunction "2_2") (pintype "passive"))
      (node (ref "R1") (pin "2") (pinfunction "2_2") (pintype "passive"))
      (node (ref "TP8") (pin "1") (pinfunction "1_1") (pintype "passive"))
      (node (ref "U2") (pin "1") (pinfunction "VDD_1") (pintype "power_in"))
    )
    (net (code "41") (name "Net-(U3-VDD)") (class "Default")
      (node (ref "C5") (pin "2") (pinfunction "2_2") (pintype "passive"))
      (node (ref "R2") (pin "2") (pinfunction "2_2") (pintype "passive"))
      (node (ref "TP5") (pin "1") (pinfunction "1_1") (pintype "passive"))
      (node (ref "U3") (pin "1") (pinfunction "VDD_1") (pintype "power_in"))
    )
    (net (code "42") (name "Net-(U4-VDD)") (class "Default")
      (node (ref "C7") (pin "2") (pinfunction "2_2") (pintype "passive"))
      (node (ref "R7") (pin "2") (pinfunction "2_2") (pintype "passive"))
      (node (ref "TP6") (pin "1") (pinfunction "1_1") (pintype "passive"))
      (node (ref "U4") (pin "1") (pinfunction "VDD_1") (pintype "power_in"))
    )
    (net (code "43") (name "Net-(U5-VDD)") (class "Default")
      (node (ref "C8") (pin "2") (pinfunction "2_2") (pintype "passive"))
      (node (ref "R8") (pin "2") (pinfunction "2_2") (pintype "passive"))
      (node (ref "TP7") (pin "1") (pinfunction "1_1") (pintype "passive"))
      (node (ref "U5") (pin "1") (pinfunction "VDD_1") (pintype "power_in"))
    )
    (net (code "44") (name "Net-(U6-VDD)") (class "Default")
      (node (ref "C9") (pin "2") (pinfunction "2_2") (pintype "passive"))
      (node (ref "R11") (pin "2") (pinfunction "2_2") (pintype "passive"))
      (node (ref "TP4") (pin "1") (pinfunction "1_1") (pintype "passive"))
      (node (ref "U6") (pin "1") (pinfunction "VDD_1") (pintype "power_in"))
    )
    (net (code "45") (name "Net-(U7-VDD)") (class "Default")
      (node (ref "C10") (pin "2") (pinfunction "2_2") (pintype "passive"))
      (node (ref "R12") (pin "2") (pinfunction "2_2") (pintype "passive"))
      (node (ref "TP9") (pin "1") (pinfunction "1_1") (pintype "passive"))
      (node (ref "U7") (pin "1") (pinfunction "VDD_1") (pintype "power_in"))
    )
    (net (code "46") (name "Net-(U8-BDS)") (class "Default")
      (node (ref "C16") (pin "1") (pinfunction "1_1") (pintype "passive"))
      (node (ref "U8") (pin "5") (pinfunction "BDS_5") (pintype "passive"))
    )
    (net (code "47") (name "Net-(U8-COMP)") (class "Default")
      (node (ref "C13") (pin "1") (pinfunction "1_1") (pintype "passive"))
      (node (ref "C24") (pin "1") (pinfunction "1_1") (pintype "passive"))
      (node (ref "U8") (pin "3") (pinfunction "COMP_3") (pintype "passive"))
    )
    (net (code "48") (name "Net-(U8-EN)") (class "Default")
      (node (ref "R15") (pin "1") (pinfunction "1_1") (pintype "passive"))
      (node (ref "U8") (pin "7") (pinfunction "EN_7") (pintype "passive"))
    )
    (net (code "49") (name "Net-(U8-FB)") (class "Default")
      (node (ref "C14") (pin "2") (pinfunction "2_2") (pintype "passive"))
      (node (ref "C19") (pin "2") (pinfunction "2_2") (pintype "passive"))
      (node (ref "FB1") (pin "1") (pinfunction "1_1") (pintype "passive"))
      (node (ref "L1") (pin "2") (pinfunction "2_2") (pintype "passive"))
      (node (ref "U8") (pin "4") (pinfunction "FB_4") (pintype "passive"))
    )
    (net (code "50") (name "VCC_5V") (class "Default")
      (node (ref "5V") (pin "1") (pinfunction "1_1") (pintype "passive"))
      (node (ref "C1") (pin "1") (pinfunction "1_1") (pintype "passive"))
      (node (ref "C15") (pin "1") (pinfunction "1_1") (pintype "passive"))
      (node (ref "C2") (pin "2") (pinfunction "2_2") (pintype "passive"))
      (node (ref "C25") (pin "1") (pinfunction "1_1") (pintype "passive"))
      (node (ref "C26") (pin "1") (pinfunction "1_1") (pintype "passive"))
      (node (ref "FB1") (pin "2") (pinfunction "2_2") (pintype "passive"))
      (node (ref "J1") (pin "2") (pinfunction "2_2") (pintype "power_in"))
      (node (ref "R1") (pin "1") (pinfunction "1_1") (pintype "passive"))
      (node (ref "R10") (pin "1") (pinfunction "1_1") (pintype "passive"))
      (node (ref "R11") (pin "1") (pinfunction "1_1") (pintype "passive"))
      (node (ref "R12") (pin "1") (pinfunction "1_1") (pintype "passive"))
      (node (ref "R13") (pin "1") (pinfunction "1_1") (pintype "passive"))
      (node (ref "R14") (pin "1") (pinfunction "1_1") (pintype "passive"))
      (node (ref "R2") (pin "1") (pinfunction "1_1") (pintype "passive"))
      (node (ref "R27") (pin "2") (pinfunction "2_2") (pintype "passive"))
      (node (ref "R28") (pin "2") (pinfunction "2_2") (pintype "passive"))
      (node (ref "R29") (pin "2") (pinfunction "2_2") (pintype "passive"))
      (node (ref "R3") (pin "1") (pinfunction "1_1") (pintype "passive"))
      (node (ref "R4") (pin "1") (pinfunction "1_1") (pintype "passive"))
      (node (ref "R5") (pin "2") (pinfunction "2_2") (pintype "passive"))
      (node (ref "R7") (pin "1") (pinfunction "1_1") (pintype "passive"))
      (node (ref "R8") (pin "1") (pinfunction "1_1") (pintype "passive"))
      (node (ref "R9") (pin "1") (pinfunction "1_1") (pintype "passive"))
      (node (ref "U1") (pin "9") (pinfunction "VDD_9") (pintype "passive"))
      (node (ref "U10") (pin "1") (pinfunction "S1_1") (pintype "passive"))
      (node (ref "U10") (pin "4") (pinfunction "S2_4") (pintype "passive"))
      (node (ref "U9") (pin "1") (pinfunction "S1_1") (pintype "passive"))
      (node (ref "U9") (pin "4") (pinfunction "S2_4") (pintype "passive"))
    )
    (net (code "51") (name "VCC_IN") (class "Default")
      (node (ref "C11") (pin "2") (pinfunction "2_2") (pintype "passive"))
      (node (ref "C12") (pin "1") (pinfunction "1_1") (pintype "passive"))
      (node (ref "C18") (pin "2") (pinfunction "2_2") (pintype "passive"))
      (node (ref "C28") (pin "2") (pinfunction "2_2") (pintype "passive"))
      (node (ref "FB2") (pin "2") (pinfunction "2_2") (pintype "passive"))
      (node (ref "L2") (pin "5") (pinfunction "5_5") (pintype "passive"))
      (node (ref "R15") (pin "2") (pinfunction "2_2") (pintype "passive"))
      (node (ref "U8") (pin "8") (pinfunction "VS_8") (pintype "passive"))
    )
    (net (code "52") (name "unconnected-(FID1-Pad0)") (class "Default")
      (node (ref "FID1") (pin "0") (pinfunction "0_0") (pintype "passive+no_connect"))
    )
    (net (code "53") (name "unconnected-(FID2-Pad0)") (class "Default")
      (node (ref "FID2") (pin "0") (pinfunction "0_0") (pintype "passive+no_connect"))
    )
    (net (code "54") (name "unconnected-(FID3-Pad0)") (class "Default")
      (node (ref "FID3") (pin "0") (pinfunction "0_0") (pintype "passive+no_connect"))
    )
    (net (code "55") (name "unconnected-(FID4-Pad0)") (class "Default")
      (node (ref "FID4") (pin "0") (pinfunction "0_0") (pintype "passive+no_connect"))
    )
    (net (code "56") (name "unconnected-(U1-PA1{slash}OSCIN-Pad5)") (class "Default")
      (node (ref "U1") (pin "5") (pinfunction "PA1/OSCIN_5") (pintype "passive+no_connect"))
    )
    (net (code "57") (name "unconnected-(U1-PA2{slash}OSCOUT-Pad6)") (class "Default")
      (node (ref "U1") (pin "6") (pinfunction "PA2/OSCOUT_6") (pintype "passive+no_connect"))
    )
  )
)
